# TataconUSB.net
KiCad netlist of a schematic drawn in Altium Designer
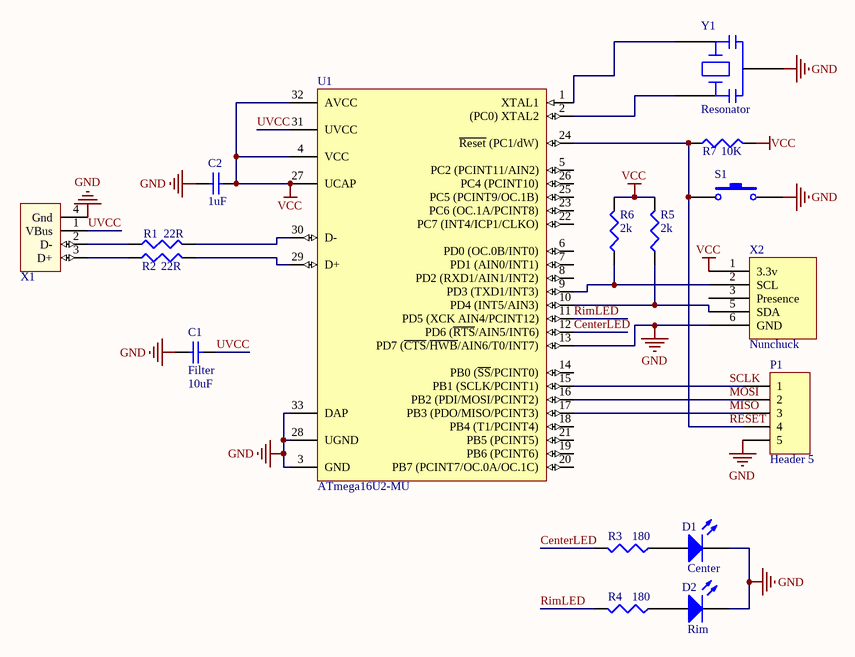
[diagram p0: TataconUSB.SchDoc]

(export (version "E")
  (design (tool "Eeschema 10.0.6"))
  (components
    (comp (ref "C1")
      (value "Filter")
      (footprint "0805")
      (description "Capacitor (Semiconductor SIM Model)")
      (fields
        (field (name "ALTIUM_VALUE") "10uF")
        (field (name "SEEED PART") "302010178")
        (field (name "PUBLISHER") "Altium Limited")
      )
      (libsource (lib "Miscellaneous Devices") (part "Cap Semi"))
    )
    (comp (ref "C2")
      (value "1uF")
      (footprint "1608[0603]")
      (description "Capacitor (Semiconductor SIM Model)")
      (fields
        (field (name "SEEED PART") "302010139")
        (field (name "Comment") "Cap Semi")
        (field (name "PUBLISHER") "Altium Limited")
      )
      (libsource (lib "Miscellaneous Devices") (part "Cap Semi"))
    )
    (comp (ref "D1")
      (value "Center")
      (footprint "LED_0603")
      (description "Typical RED, GREEN, YELLOW, AMBER GaAs LED")
      (fields (field (name "SEEED PART") "304090042") (field (name "PUBLISHER") "Altium Limited"))
      (libsource (lib "Miscellaneous Devices") (part "LED2"))
    )
    (comp (ref "D2")
      (value "Rim")
      (footprint "LED_0603")
      (description "Typical RED, GREEN, YELLOW, AMBER GaAs LED")
      (fields (field (name "SEEED PART") "304090045") (field (name "PUBLISHER") "Altium Limited"))
      (libsource (lib "Miscellaneous Devices") (part "LED2"))
    )
    (comp (ref "P1")
      (value "Header 5")
      (footprint "HDR1X5")
      (description "Header, 5-Pin")
      (fields (field (name "PUBLISHER") "Altium Limited"))
      (libsource (lib "Miscellaneous Connectors") (part "Header 5"))
    )
    (comp (ref "R1")
      (value "22R")
      (footprint "J1-0603")
      (description "Resistor")
      (fields
        (field (name "SEEED PART") "301010289")
        (field (name "Comment") "Res3")
        (field (name "PUBLISHER") "Altium Limited")
      )
      (libsource (lib "Miscellaneous Devices") (part "Res3"))
    )
    (comp (ref "R2")
      (value "22R")
      (footprint "J1-0603")
      (description "Resistor")
      (fields
        (field (name "SEEED PART") "301010289")
        (field (name "Comment") "Res3")
        (field (name "PUBLISHER") "Altium Limited")
      )
      (libsource (lib "Miscellaneous Devices") (part "Res3"))
    )
    (comp (ref "R3")
      (value "180")
      (footprint "J1-0603")
      (description "Resistor")
      (fields
        (field (name "SEEED PART") "301010163")
        (field (name "Comment") "Res3")
        (field (name "PUBLISHER") "Altium Limited")
      )
      (libsource (lib "Miscellaneous Devices") (part "Res3"))
    )
    (comp (ref "R4")
      (value "180")
      (footprint "J1-0603")
      (description "Resistor")
      (fields
        (field (name "SEEED PART") "301010163")
        (field (name "Comment") "Res3")
        (field (name "PUBLISHER") "Altium Limited")
      )
      (libsource (lib "Miscellaneous Devices") (part "Res3"))
    )
    (comp (ref "R5")
      (value "2k")
      (footprint "J1-0603")
      (description "Resistor")
      (fields
        (field (name "SEEED PART") "301010289")
        (field (name "Comment") "Res3")
        (field (name "PUBLISHER") "Altium Limited")
      )
      (libsource (lib "Miscellaneous Devices") (part "Res3"))
    )
    (comp (ref "R6")
      (value "2k")
      (footprint "J1-0603")
      (description "Resistor")
      (fields
        (field (name "SEEED PART") "301010289")
        (field (name "Comment") "Res3")
        (field (name "PUBLISHER") "Altium Limited")
      )
      (libsource (lib "Miscellaneous Devices") (part "Res3"))
    )
    (comp (ref "R7")
      (value "10K")
      (footprint "J1-0603")
      (description "Resistor")
      (fields (field (name "SEEED PART") "301010299") (field (name "PUBLISHER") "Altium Limited"))
      (libsource (lib "Miscellaneous Devices") (part "Res3"))
    )
    (comp (ref "S1")
      (value "SW-PB")
      (footprint "SKQGADE010")
      (description "Switch")
      (fields
        (field (name "SEEED PART") "311020017")
        (field (name "MANUFACTURER PART") "SKQGADE010")
        (field (name "PUBLISHER") "Altium Limited")
      )
      (libsource (lib "Miscellaneous Devices") (part "SW-PB"))
    )
    (comp (ref "U1")
      (value "ATmega16U2-MU")
      (footprint "32PG_N")
      (fields (field (name "SEEED PART") "310010018") (field (name "PUBLISHER") "Altium Limited"))
      (libsource (lib "Atmel Microcontroller 8-Bit megaAVR") (part "ATmega16U2-MU"))
    )
    (comp (ref "X1")
      (value "USB Connector")
      (footprint "USB_A_MALE")
      (libsource (lib "MonParts") (part "USB Connector"))
    )
    (comp (ref "X2") (value "Nunchuck") (footprint "NUNCHUCK") (libsource (lib "MonParts") (part "Nunchuck")))
    (comp (ref "Y1")
      (value "Resonator")
      (footprint "RESONATOR")
      (libsource (lib "MonParts") (part "Resonator"))
    )
  )
  (nets
    (net (code "1") (name "/CenterLED") (class "Default")
      (node (ref "R3") (pin "2") (pinfunction "2_2") (pintype "passive"))
      (node (ref "U1") (pin "12") (pinfunction "PD6_(~{RTS}/AIN5/INT6)_12") (pintype "bidirectional"))
    )
    (net (code "2") (name "/MISO") (class "Default")
      (node (ref "P1") (pin "3") (pinfunction "3_3") (pintype "passive"))
      (node (ref "U1") (pin "17") (pinfunction "PB3_(PDO/MISO/PCINT3)_17") (pintype "bidirectional"))
    )
    (net (code "3") (name "/MOSI") (class "Default")
      (node (ref "P1") (pin "2") (pinfunction "2_2") (pintype "passive"))
      (node (ref "U1") (pin "16") (pinfunction "PB2_(PDI/MOSI/PCINT2)_16") (pintype "bidirectional"))
    )
    (net (code "4") (name "/RESET") (class "Default")
      (node (ref "P1") (pin "4") (pinfunction "4_4") (pintype "passive"))
      (node (ref "R7") (pin "1") (pinfunction "1_1") (pintype "passive"))
      (node (ref "S1") (pin "1") (pinfunction "1_1") (pintype "passive"))
      (node (ref "U1") (pin "24") (pinfunction "~{Reset}_(PC1/dW)_24") (pintype "bidirectional"))
    )
    (net (code "5") (name "/RimLED") (class "Default")
      (node (ref "R4") (pin "2") (pinfunction "2_2") (pintype "passive"))
      (node (ref "U1") (pin "11") (pinfunction "PD5_(XCK_AIN4/PCINT12)_11") (pintype "bidirectional"))
    )
    (net (code "6") (name "/SCLK") (class "Default")
      (node (ref "P1") (pin "1") (pinfunction "1_1") (pintype "passive"))
      (node (ref "U1") (pin "15") (pinfunction "PB1_(SCLK/PCINT1)_15") (pintype "bidirectional"))
    )
    (net (code "7") (name "/UVCC") (class "Default")
      (node (ref "C1") (pin "1") (pinfunction "1_1") (pintype "passive"))
      (node (ref "U1") (pin "31") (pinfunction "UVCC_31") (pintype "power_in"))
      (node (ref "X1") (pin "1") (pinfunction "VBus_1") (pintype "power_in"))
    )
    (net (code "8") (name "GND") (class "Default")
      (node (ref "C1") (pin "2") (pinfunction "2_2") (pintype "passive"))
      (node (ref "C2") (pin "2") (pinfunction "2_2") (pintype "passive"))
      (node (ref "D1") (pin "2") (pinfunction "K_2") (pintype "passive"))
      (node (ref "D2") (pin "2") (pinfunction "K_2") (pintype "passive"))
      (node (ref "P1") (pin "5") (pinfunction "5_5") (pintype "passive"))
      (node (ref "S1") (pin "2") (pinfunction "2_2") (pintype "passive"))
      (node (ref "U1") (pin "13") (pinfunction "PD7_(~{CTS}/~{HWB}/AIN6/T0/INT7)_13") (pintype "bidirectional"))
      (node (ref "U1") (pin "28") (pinfunction "UGND_28") (pintype "power_in"))
      (node (ref "U1") (pin "3") (pinfunction "GND_3") (pintype "power_in"))
      (node (ref "U1") (pin "33") (pinfunction "DAP_33") (pintype "power_in"))
      (node (ref "X1") (pin "4") (pinfunction "Gnd_4") (pintype "power_in"))
      (node (ref "X2") (pin "6") (pinfunction "GND_6") (pintype "passive"))
      (node (ref "Y1") (pin "2") (pinfunction "2_2") (pintype "passive"))
    )
    (net (code "9") (name "Net-(D1-A)") (class "Default")
      (node (ref "D1") (pin "1") (pinfunction "A_1") (pintype "passive"))
      (node (ref "R3") (pin "1") (pinfunction "1_1") (pintype "passive"))
    )
    (net (code "10") (name "Net-(D2-A)") (class "Default")
      (node (ref "D2") (pin "1") (pinfunction "A_1") (pintype "passive"))
      (node (ref "R4") (pin "1") (pinfunction "1_1") (pintype "passive"))
    )
    (net (code "11") (name "Net-(U1-(PC0)_XTAL2)") (class "Default")
      (node (ref "U1") (pin "2") (pinfunction "(PC0)_XTAL2_2") (pintype "bidirectional"))
      (node (ref "Y1") (pin "1") (pinfunction "1_1") (pintype "passive"))
    )
    (net (code "12") (name "Net-(U1-D+)") (class "Default")
      (node (ref "R2") (pin "2") (pinfunction "2_2") (pintype "passive"))
      (node (ref "U1") (pin "29") (pinfunction "D+_29") (pintype "bidirectional"))
    )
    (net (code "13") (name "Net-(U1-D-)") (class "Default")
      (node (ref "R1") (pin "2") (pinfunction "2_2") (pintype "passive"))
      (node (ref "U1") (pin "30") (pinfunction "D-_30") (pintype "bidirectional"))
    )
    (net (code "14") (name "Net-(U1-PD3_(TXD1{slash}INT3))") (class "Default")
      (node (ref "R6") (pin "1") (pinfunction "1_1") (pintype "passive"))
      (node (ref "U1") (pin "9") (pinfunction "PD3_(TXD1/INT3)_9") (pintype "bidirectional"))
      (node (ref "X2") (pin "2") (pinfunction "SCL_2") (pintype "passive"))
    )
    (net (code "15") (name "Net-(U1-PD4_(INT5{slash}AIN3))") (class "Default")
      (node (ref "R5") (pin "1") (pinfunction "1_1") (pintype "passive"))
      (node (ref "U1") (pin "10") (pinfunction "PD4_(INT5/AIN3)_10") (pintype "bidirectional"))
      (node (ref "X2") (pin "5") (pinfunction "SDA_5") (pintype "passive"))
    )
    (net (code "16") (name "Net-(U1-XTAL1)") (class "Default")
      (node (ref "U1") (pin "1") (pinfunction "XTAL1_1") (pintype "input"))
      (node (ref "Y1") (pin "3") (pinfunction "1_3") (pintype "passive"))
    )
    (net (code "17") (name "Net-(X1-D+)") (class "Default")
      (node (ref "R2") (pin "1") (pinfunction "1_1") (pintype "passive"))
      (node (ref "X1") (pin "3") (pinfunction "D+_3") (pintype "bidirectional"))
    )
    (net (code "18") (name "Net-(X1-D-)") (class "Default")
      (node (ref "R1") (pin "1") (pinfunction "1_1") (pintype "passive"))
      (node (ref "X1") (pin "2") (pinfunction "D-_2") (pintype "bidirectional"))
    )
    (net (code "19") (name "VCC") (class "Default")
      (node (ref "C2") (pin "1") (pinfunction "1_1") (pintype "passive"))
      (node (ref "R5") (pin "2") (pinfunction "2_2") (pintype "passive"))
      (node (ref "R6") (pin "2") (pinfunction "2_2") (pintype "passive"))
      (node (ref "R7") (pin "2") (pinfunction "2_2") (pintype "passive"))
      (node (ref "U1") (pin "27") (pinfunction "UCAP_27") (pintype "power_in"))
      (node (ref "U1") (pin "32") (pinfunction "AVCC_32") (pintype "power_in"))
      (node (ref "U1") (pin "4") (pinfunction "VCC_4") (pintype "power_in"))
      (node (ref "X2") (pin "1") (pinfunction "3.3v_1") (pintype "passive"))
    )
    (net (code "20") (name "unconnected-(U1-PB0_(~{SS}{slash}PCINT0)-Pad14)") (class "Default")
      (node (ref "U1") (pin "14") (pinfunction "PB0_(~{SS}/PCINT0)_14") (pintype "bidirectional"))
    )
    (net (code "21") (name "unconnected-(U1-PB4_(T1{slash}PCINT4)-Pad18)") (class "Default")
      (node (ref "U1") (pin "18") (pinfunction "PB4_(T1/PCINT4)_18") (pintype "bidirectional"))
    )
    (net (code "22") (name "unconnected-(U1-PB5_(PCINT5)-Pad21)") (class "Default")
      (node (ref "U1") (pin "21") (pinfunction "PB5_(PCINT5)_21") (pintype "bidirectional"))
    )
    (net (code "23") (name "unconnected-(U1-PB6_(PCINT6)-Pad19)") (class "Default")
      (node (ref "U1") (pin "19") (pinfunction "PB6_(PCINT6)_19") (pintype "bidirectional"))
    )
    (net (code "24") (name "unconnected-(U1-PB7_(PCINT7{slash}OC.0A{slash}OC.1C)-Pad20)") (class "Default")
      (node (ref "U1") (pin "20") (pinfunction "PB7_(PCINT7/OC.0A/OC.1C)_20") (pintype "bidirectional"))
    )
    (net (code "25") (name "unconnected-(U1-PC2_(PCINT11{slash}AIN2)-Pad5)") (class "Default")
      (node (ref "U1") (pin "5") (pinfunction "PC2_(PCINT11/AIN2)_5") (pintype "bidirectional"))
    )
    (net (code "26") (name "unconnected-(U1-PC4_(PCINT10)-Pad26)") (class "Default")
      (node (ref "U1") (pin "26") (pinfunction "PC4_(PCINT10)_26") (pintype "bidirectional"))
    )
    (net (code "27") (name "unconnected-(U1-PC5_(PCINT9{slash}OC.1B)-Pad25)") (class "Default")
      (node (ref "U1") (pin "25") (pinfunction "PC5_(PCINT9/OC.1B)_25") (pintype "bidirectional"))
    )
    (net (code "28") (name "unconnected-(U1-PC6_(OC.1A{slash}PCINT8)-Pad23)") (class "Default")
      (node (ref "U1") (pin "23") (pinfunction "PC6_(OC.1A/PCINT8)_23") (pintype "bidirectional"))
    )
    (net (code "29") (name "unconnected-(U1-PC7_(INT4{slash}ICP1{slash}CLKO)-Pad22)") (class "Default")
      (node (ref "U1") (pin "22") (pinfunction "PC7_(INT4/ICP1/CLKO)_22") (pintype "bidirectional"))
    )
    (net (code "30") (name "unconnected-(U1-PD0_(OC.0B{slash}INT0)-Pad6)") (class "Default")
      (node (ref "U1") (pin "6") (pinfunction "PD0_(OC.0B/INT0)_6") (pintype "bidirectional"))
    )
    (net (code "31") (name "unconnected-(U1-PD1_(AIN0{slash}INT1)-Pad7)") (class "Default")
      (node (ref "U1") (pin "7") (pinfunction "PD1_(AIN0/INT1)_7") (pintype "bidirectional"))
    )
    (net (code "32") (name "unconnected-(U1-PD2_(RXD1{slash}AIN1{slash}INT2)-Pad8)") (class "Default")
      (node (ref "U1") (pin "8") (pinfunction "PD2_(RXD1/AIN1/INT2)_8") (pintype "bidirectional"))
    )
    (net (code "33") (name "unconnected-(X2-Presence-Pad3)") (class "Default")
      (node (ref "X2") (pin "3") (pinfunction "Presence_3") (pintype "passive"))
    )
  )
)
